# mainboard_mcu_v1_5.net
KiCad netlist of a schematic drawn in Altium Designer
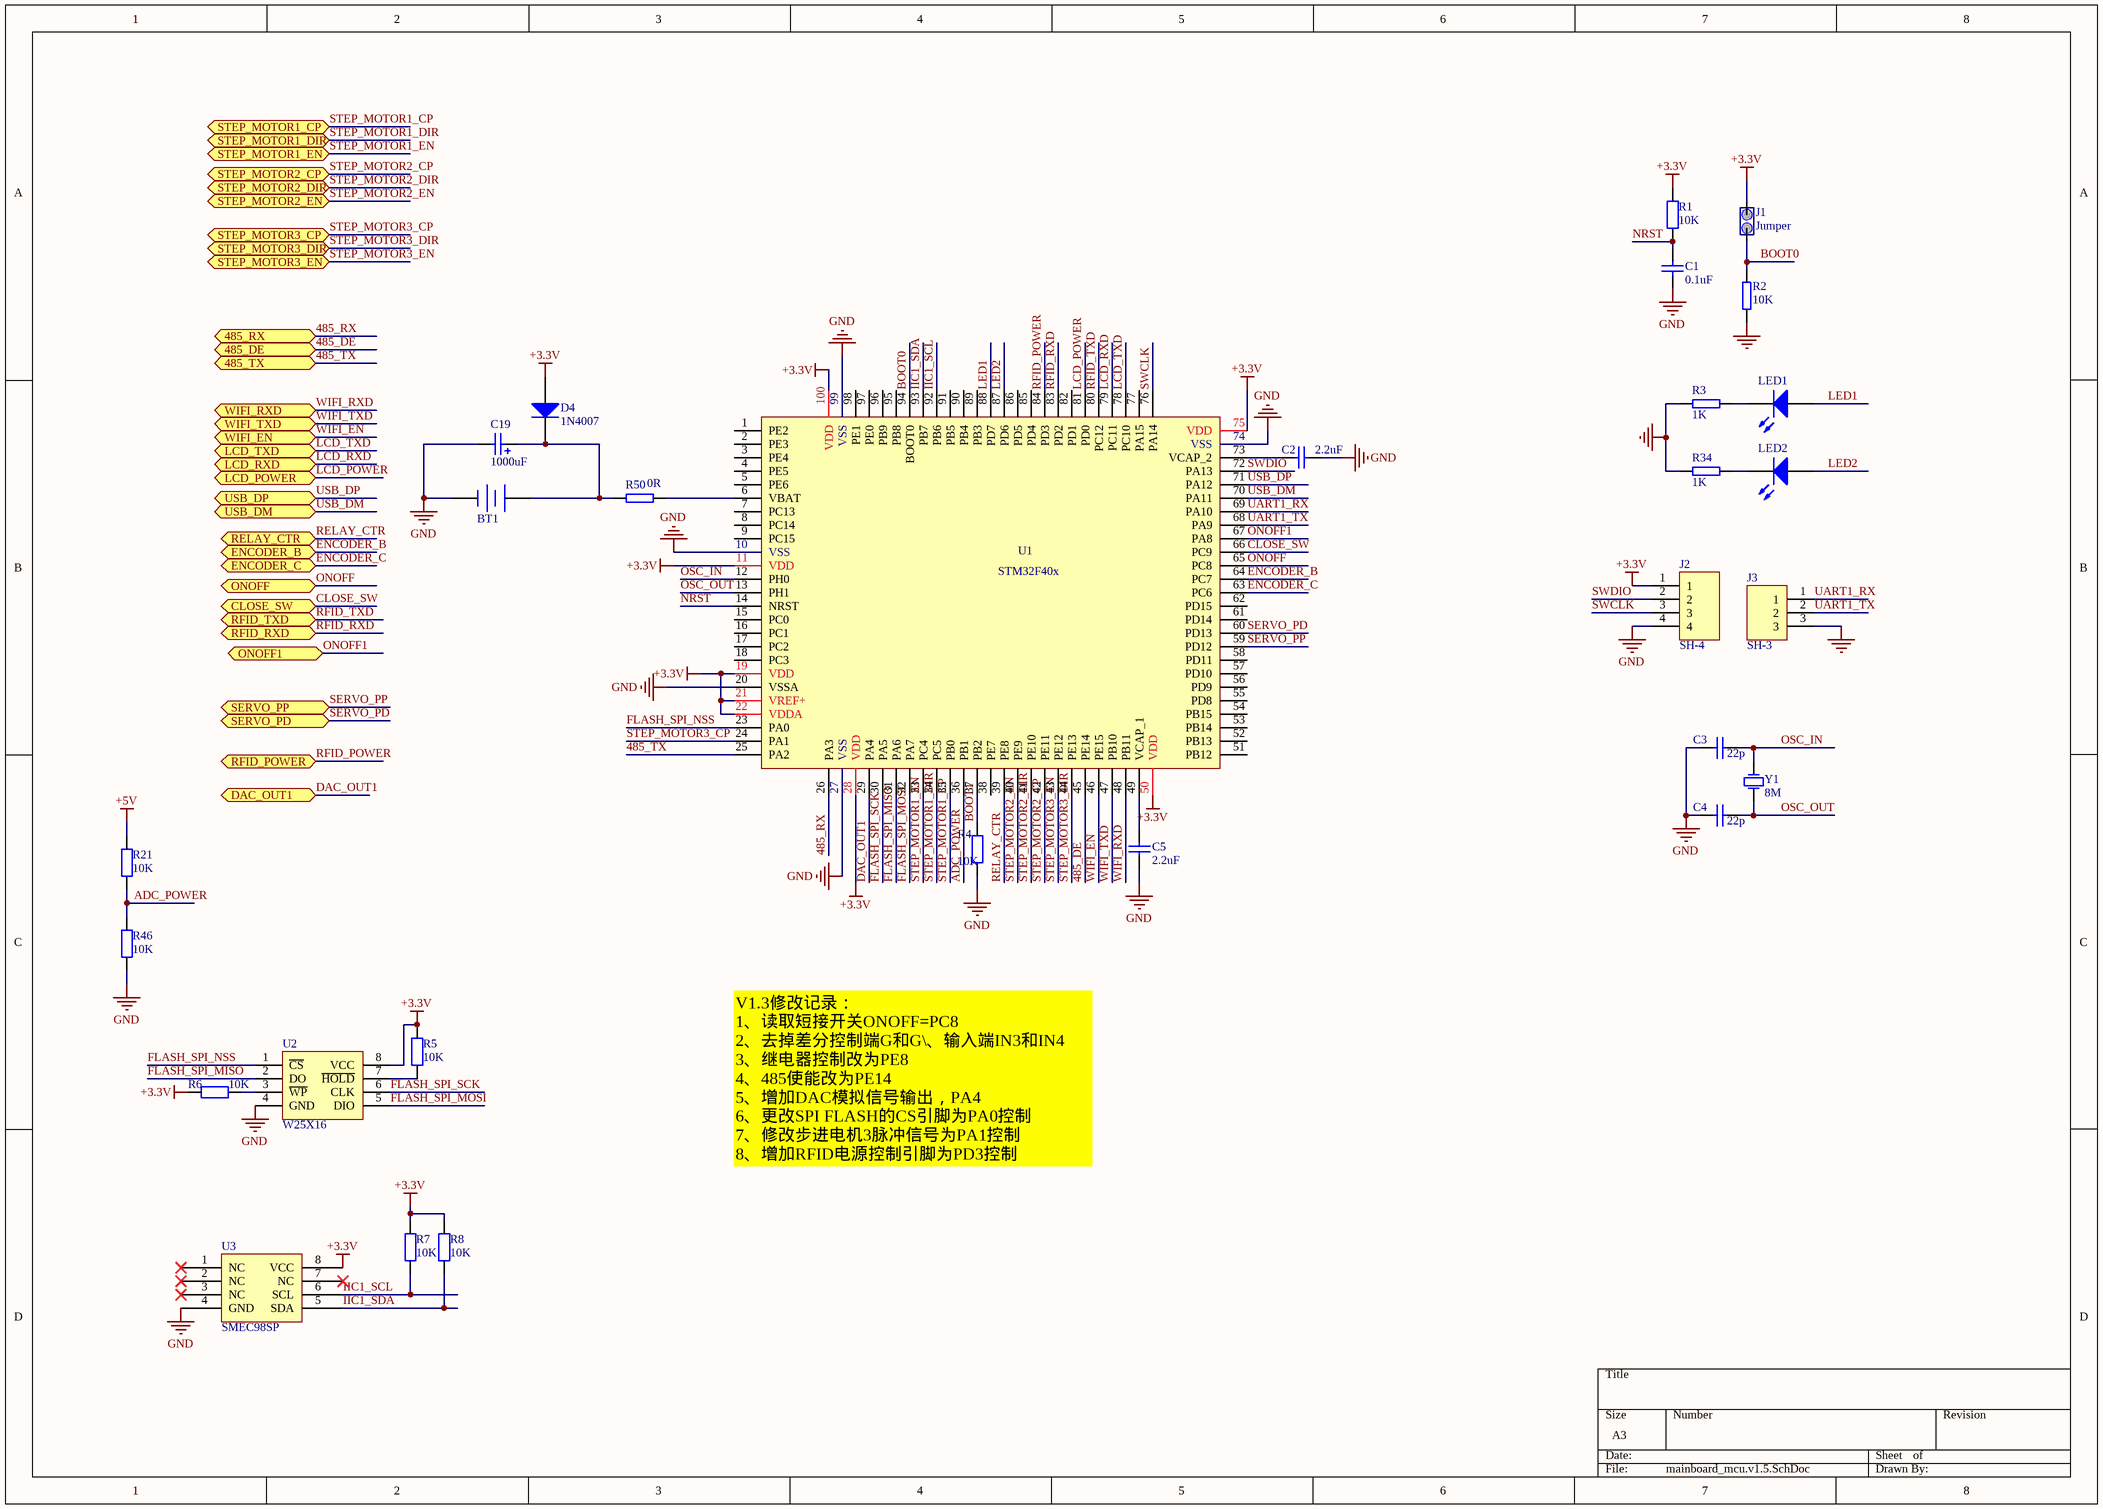
[diagram p0: mainboard_mcu.v1.5.SchDoc]

(export (version "E")
  (design (tool "Eeschema 10.0.6"))
  (components
    (comp (ref "BT1")
      (value "CR1220")
      (footprint "CR1220")
      (description "Multicell Battery")
      (fields (field (name "PUBLISHER") "Altium Limited"))
      (libsource (lib "Miscellaneous Devices") (part "Battery"))
    )
    (comp (ref "C1")
      (value "0.1uF")
      (footprint "0805")
      (description "Capacitor")
      (fields (field (name "PUBLISHER") "Altium Limited"))
      (libsource (lib "TIAN's Schlib") (part "Cap"))
    )
    (comp (ref "C2")
      (value "2.2uF")
      (footprint "0805")
      (description "Capacitor")
      (fields (field (name "PUBLISHER") "Altium Limited"))
      (libsource (lib "TIAN's Schlib") (part "Cap"))
    )
    (comp (ref "C3")
      (value "22p")
      (footprint "0805")
      (description "Capacitor")
      (fields (field (name "PUBLISHER") "Altium Limited"))
      (libsource (lib "TIAN's Schlib") (part "Cap"))
    )
    (comp (ref "C4")
      (value "22p")
      (footprint "0805")
      (description "Capacitor")
      (fields (field (name "PUBLISHER") "Altium Limited"))
      (libsource (lib "TIAN's Schlib") (part "Cap"))
    )
    (comp (ref "C5")
      (value "2.2uF")
      (footprint "0805")
      (description "Capacitor")
      (fields (field (name "PUBLISHER") "Altium Limited"))
      (libsource (lib "TIAN's Schlib") (part "Cap"))
    )
    (comp (ref "C19")
      (value "1000uF")
      (footprint "CAP_SMT_10X10")
      (description "Polarized Capacitor (Radial)")
      (fields (field (name "PUBLISHER") "Altium Limited"))
      (libsource (lib "Miscellaneous Devices") (part "Cap Pol1"))
    )
    (comp (ref "D4")
      (value "1N4007")
      (footprint "Diode_TP")
      (description "Default Diode")
      (fields (field (name "PUBLISHER") "Altium Limited"))
      (libsource (lib "Miscellaneous Devices") (part "Diode"))
    )
    (comp (ref "J1") (value "Jumper") (footprint "J254-2") (libsource (lib "Connector") (part "Jumper")))
    (comp (ref "J2") (value "SH-4") (footprint "J254-4") (libsource (lib "Connector") (part "SH-4")))
    (comp (ref "J3") (value "SH-3") (footprint "J2.54-3") (libsource (lib "Connector") (part "SH-3")))
    (comp (ref "LED1")
      (value "GREEN")
      (footprint "LED")
      (description "Typical RED, GREEN, YELLOW, AMBER GaAs LED")
      (fields (field (name "PUBLISHER") "Altium Limited"))
      (libsource (lib "Miscellaneous Devices") (part "LED2"))
    )
    (comp (ref "LED2")
      (value "GREEN")
      (footprint "LED")
      (description "Typical RED, GREEN, YELLOW, AMBER GaAs LED")
      (fields (field (name "PUBLISHER") "Altium Limited"))
      (libsource (lib "Miscellaneous Devices") (part "LED2"))
    )
    (comp (ref "R1")
      (value "10K")
      (footprint "0805")
      (description "Resistor")
      (fields (field (name "PUBLISHER") "Altium Limited"))
      (libsource (lib "") (part "Res2_1"))
    )
    (comp (ref "R2")
      (value "10K")
      (footprint "0805")
      (description "电阻")
      (libsource (lib "Component") (part "RES"))
    )
    (comp (ref "R3")
      (value "1K")
      (footprint "0805")
      (description "电阻")
      (libsource (lib "Component") (part "RES"))
    )
    (comp (ref "R4")
      (value "10K")
      (footprint "0805")
      (description "Resistor")
      (fields (field (name "PUBLISHER") "Altium Limited"))
      (libsource (lib "") (part "Res2_2"))
    )
    (comp (ref "R5")
      (value "10K")
      (footprint "0805")
      (description "Resistor")
      (fields (field (name "PUBLISHER") "Altium Limited"))
      (libsource (lib "") (part "Res2_2"))
    )
    (comp (ref "R6")
      (value "10K")
      (footprint "0805")
      (description "Resistor")
      (fields (field (name "PUBLISHER") "Altium Limited"))
      (libsource (lib "TIAN's Schlib") (part "Res2"))
    )
    (comp (ref "R7")
      (value "10K")
      (footprint "0805")
      (description "Resistor")
      (fields (field (name "PUBLISHER") "Altium Limited"))
      (libsource (lib "") (part "Res2_1"))
    )
    (comp (ref "R8")
      (value "10K")
      (footprint "0805")
      (description "Resistor")
      (fields (field (name "PUBLISHER") "Altium Limited"))
      (libsource (lib "") (part "Res2_1"))
    )
    (comp (ref "R21")
      (value "10K")
      (footprint "0805")
      (description "Resistor")
      (fields (field (name "PUBLISHER") "Altium Limited"))
      (libsource (lib "") (part "Res2_1"))
    )
    (comp (ref "R34")
      (value "1K")
      (footprint "0805")
      (description "电阻")
      (libsource (lib "Component") (part "RES"))
    )
    (comp (ref "R46")
      (value "10K")
      (footprint "0805")
      (description "Resistor")
      (fields (field (name "PUBLISHER") "Altium Limited"))
      (libsource (lib "") (part "Res2_1"))
    )
    (comp (ref "R50")
      (value "0R")
      (footprint "0805")
      (description "电阻")
      (libsource (lib "Component") (part "RES"))
    )
    (comp (ref "U1") (value "STM32F40x") (footprint "TQFP100") (libsource (lib "Chip") (part "STM32F40x")))
    (comp (ref "U2") (value "W25X16") (footprint "SOP8") (libsource (lib "Chip") (part "W25X16")))
    (comp (ref "U3") (value "SMEC98SP") (footprint "SO-8") (libsource (lib "Chip") (part "SMEC98SP")))
    (comp (ref "Y1")
      (value "8M")
      (footprint "XTAL")
      (description "Crystal Oscillator")
      (fields (field (name "PUBLISHER") "Altium Limited"))
      (libsource (lib "TIAN's Schlib") (part "X-32.768"))
    )
  )
  (nets
    (net (code "1") (name "+3.3V") (class "Default")
      (node (ref "D4") (pin "1") (pinfunction "A_1") (pintype "passive"))
      (node (ref "J1") (pin "2") (pinfunction "2_2") (pintype "passive"))
      (node (ref "J2") (pin "1") (pinfunction "1_1") (pintype "passive"))
      (node (ref "R1") (pin "2") (pinfunction "2_2") (pintype "passive"))
      (node (ref "R5") (pin "1") (pinfunction "1_1") (pintype "passive"))
      (node (ref "R6") (pin "2") (pinfunction "2_2") (pintype "passive"))
      (node (ref "R7") (pin "2") (pinfunction "2_2") (pintype "passive"))
      (node (ref "R8") (pin "2") (pinfunction "2_2") (pintype "passive"))
      (node (ref "U1") (pin "100") (pinfunction "VDD_100") (pintype "passive"))
      (node (ref "U1") (pin "11") (pinfunction "VDD_11") (pintype "passive"))
      (node (ref "U1") (pin "19") (pinfunction "VDD_19") (pintype "passive"))
      (node (ref "U1") (pin "21") (pinfunction "VREF+_21") (pintype "passive"))
      (node (ref "U1") (pin "22") (pinfunction "VDDA_22") (pintype "passive"))
      (node (ref "U1") (pin "28") (pinfunction "VDD_28") (pintype "passive"))
      (node (ref "U1") (pin "50") (pinfunction "VDD_50") (pintype "passive"))
      (node (ref "U1") (pin "75") (pinfunction "VDD_75") (pintype "passive"))
      (node (ref "U2") (pin "8") (pinfunction "VCC_8") (pintype "passive"))
      (node (ref "U3") (pin "8") (pinfunction "VCC_8") (pintype "passive"))
    )
    (net (code "2") (name "+5V") (class "Default")
      (node (ref "R21") (pin "2") (pinfunction "2_2") (pintype "passive"))
    )
    (net (code "3") (name "/485_DE") (class "Default")
      (node (ref "U1") (pin "45") (pinfunction "PE14_45") (pintype "passive"))
    )
    (net (code "4") (name "/485_RX") (class "Default")
      (node (ref "U1") (pin "26") (pinfunction "PA3_26") (pintype "passive"))
    )
    (net (code "5") (name "/485_TX") (class "Default")
      (node (ref "U1") (pin "25") (pinfunction "PA2_25") (pintype "passive"))
    )
    (net (code "6") (name "/ADC_POWER") (class "Default")
      (node (ref "R21") (pin "1") (pinfunction "1_1") (pintype "passive"))
      (node (ref "R46") (pin "2") (pinfunction "2_2") (pintype "passive"))
      (node (ref "U1") (pin "36") (pinfunction "PB1_36") (pintype "passive"))
    )
    (net (code "7") (name "/BOOT0") (class "Default")
      (node (ref "J1") (pin "1") (pinfunction "1_1") (pintype "passive"))
      (node (ref "R2") (pin "1") (pinfunction "1_1") (pintype "passive"))
      (node (ref "U1") (pin "94") (pinfunction "BOOT0_94") (pintype "passive"))
    )
    (net (code "8") (name "/BOOT1") (class "Default")
      (node (ref "R4") (pin "1") (pinfunction "1_1") (pintype "passive"))
      (node (ref "U1") (pin "37") (pinfunction "PB2_37") (pintype "passive"))
    )
    (net (code "9") (name "/CLOSE_SW") (class "Default")
      (node (ref "U1") (pin "66") (pinfunction "PC9_66") (pintype "passive"))
    )
    (net (code "10") (name "/DAC_OUT1") (class "Default")
      (node (ref "U1") (pin "29") (pinfunction "PA4_29") (pintype "passive"))
    )
    (net (code "11") (name "/ENCODER_B") (class "Default")
      (node (ref "U1") (pin "64") (pinfunction "PC7_64") (pintype "passive"))
    )
    (net (code "12") (name "/ENCODER_C") (class "Default")
      (node (ref "U1") (pin "63") (pinfunction "PC6_63") (pintype "passive"))
    )
    (net (code "13") (name "/FLASH_SPI_MISO") (class "Default")
      (node (ref "U1") (pin "31") (pinfunction "PA6_31") (pintype "passive"))
      (node (ref "U2") (pin "2") (pinfunction "DO_2") (pintype "passive"))
    )
    (net (code "14") (name "/FLASH_SPI_MOSI") (class "Default")
      (node (ref "U1") (pin "32") (pinfunction "PA7_32") (pintype "passive"))
      (node (ref "U2") (pin "5") (pinfunction "DIO_5") (pintype "passive"))
    )
    (net (code "15") (name "/FLASH_SPI_NSS") (class "Default")
      (node (ref "U1") (pin "23") (pinfunction "PA0_23") (pintype "passive"))
      (node (ref "U2") (pin "1") (pinfunction "~{CS}_1") (pintype "passive"))
    )
    (net (code "16") (name "/FLASH_SPI_SCK") (class "Default")
      (node (ref "U1") (pin "30") (pinfunction "PA5_30") (pintype "passive"))
      (node (ref "U2") (pin "6") (pinfunction "CLK_6") (pintype "passive"))
    )
    (net (code "17") (name "/IIC1_SCL") (class "Default")
      (node (ref "R7") (pin "1") (pinfunction "1_1") (pintype "passive"))
      (node (ref "U1") (pin "92") (pinfunction "PB6_92") (pintype "passive"))
      (node (ref "U3") (pin "6") (pinfunction "SCL_6") (pintype "passive"))
    )
    (net (code "18") (name "/IIC1_SDA") (class "Default")
      (node (ref "R8") (pin "1") (pinfunction "1_1") (pintype "passive"))
      (node (ref "U1") (pin "93") (pinfunction "PB7_93") (pintype "passive"))
      (node (ref "U3") (pin "5") (pinfunction "SDA_5") (pintype "passive"))
    )
    (net (code "19") (name "/LCD_POWER") (class "Default")
      (node (ref "U1") (pin "81") (pinfunction "PD0_81") (pintype "passive"))
    )
    (net (code "20") (name "/LCD_RXD") (class "Default")
      (node (ref "U1") (pin "79") (pinfunction "PC11_79") (pintype "passive"))
    )
    (net (code "21") (name "/LCD_TXD") (class "Default")
      (node (ref "U1") (pin "78") (pinfunction "PC10_78") (pintype "passive"))
    )
    (net (code "22") (name "/LED1") (class "Default")
      (node (ref "LED1") (pin "1") (pinfunction "A_1") (pintype "passive"))
      (node (ref "U1") (pin "88") (pinfunction "PD7_88") (pintype "passive"))
    )
    (net (code "23") (name "/LED2") (class "Default")
      (node (ref "LED2") (pin "1") (pinfunction "A_1") (pintype "passive"))
      (node (ref "U1") (pin "87") (pinfunction "PD6_87") (pintype "passive"))
    )
    (net (code "24") (name "/NRST") (class "Default")
      (node (ref "C1") (pin "2") (pinfunction "2_2") (pintype "passive"))
      (node (ref "R1") (pin "1") (pinfunction "1_1") (pintype "passive"))
      (node (ref "U1") (pin "14") (pinfunction "NRST_14") (pintype "passive"))
    )
    (net (code "25") (name "/ONOFF") (class "Default")
      (node (ref "U1") (pin "65") (pinfunction "PC8_65") (pintype "passive"))
    )
    (net (code "26") (name "/ONOFF1") (class "Default")
      (node (ref "U1") (pin "67") (pinfunction "PA8_67") (pintype "passive"))
    )
    (net (code "27") (name "/OSC_IN") (class "Default")
      (node (ref "C3") (pin "1") (pinfunction "1_1") (pintype "passive"))
      (node (ref "U1") (pin "12") (pinfunction "PH0_12") (pintype "passive"))
      (node (ref "Y1") (pin "2") (pinfunction "OSC2_2") (pintype "passive"))
    )
    (net (code "28") (name "/OSC_OUT") (class "Default")
      (node (ref "C4") (pin "1") (pinfunction "1_1") (pintype "passive"))
      (node (ref "U1") (pin "13") (pinfunction "PH1_13") (pintype "passive"))
      (node (ref "Y1") (pin "1") (pinfunction "OSC1_1") (pintype "passive"))
    )
    (net (code "29") (name "/RELAY_CTR") (class "Default")
      (node (ref "U1") (pin "39") (pinfunction "PE8_39") (pintype "passive"))
    )
    (net (code "30") (name "/RFID_POWER") (class "Default")
      (node (ref "U1") (pin "84") (pinfunction "PD3_84") (pintype "passive"))
    )
    (net (code "31") (name "/RFID_RXD") (class "Default")
      (node (ref "U1") (pin "83") (pinfunction "PD2_83") (pintype "passive"))
    )
    (net (code "32") (name "/RFID_TXD") (class "Default")
      (node (ref "U1") (pin "80") (pinfunction "PC12_80") (pintype "passive"))
    )
    (net (code "33") (name "/SERVO_PD") (class "Default")
      (node (ref "U1") (pin "60") (pinfunction "PD13_60") (pintype "passive"))
    )
    (net (code "34") (name "/SERVO_PP") (class "Default")
      (node (ref "U1") (pin "59") (pinfunction "PD12_59") (pintype "passive"))
    )
    (net (code "35") (name "/STEP_MOTOR1_CP") (class "Default")
      (node (ref "U1") (pin "35") (pinfunction "PB0_35") (pintype "passive"))
    )
    (net (code "36") (name "/STEP_MOTOR1_DIR") (class "Default")
      (node (ref "U1") (pin "34") (pinfunction "PC5_34") (pintype "passive"))
    )
    (net (code "37") (name "/STEP_MOTOR1_EN") (class "Default")
      (node (ref "U1") (pin "33") (pinfunction "PC4_33") (pintype "passive"))
    )
    (net (code "38") (name "/STEP_MOTOR2_CP") (class "Default")
      (node (ref "U1") (pin "42") (pinfunction "PE11_42") (pintype "passive"))
    )
    (net (code "39") (name "/STEP_MOTOR2_DIR") (class "Default")
      (node (ref "U1") (pin "41") (pinfunction "PE10_41") (pintype "passive"))
    )
    (net (code "40") (name "/STEP_MOTOR2_EN") (class "Default")
      (node (ref "U1") (pin "40") (pinfunction "PE9_40") (pintype "passive"))
    )
    (net (code "41") (name "/STEP_MOTOR3_CP") (class "Default")
      (node (ref "U1") (pin "24") (pinfunction "PA1_24") (pintype "passive"))
    )
    (net (code "42") (name "/STEP_MOTOR3_DIR") (class "Default")
      (node (ref "U1") (pin "44") (pinfunction "PE13_44") (pintype "passive"))
    )
    (net (code "43") (name "/STEP_MOTOR3_EN") (class "Default")
      (node (ref "U1") (pin "43") (pinfunction "PE12_43") (pintype "passive"))
    )
    (net (code "44") (name "/SWCLK") (class "Default")
      (node (ref "J2") (pin "3") (pinfunction "3_3") (pintype "passive"))
      (node (ref "U1") (pin "76") (pinfunction "PA14_76") (pintype "passive"))
    )
    (net (code "45") (name "/SWDIO") (class "Default")
      (node (ref "J2") (pin "2") (pinfunction "2_2") (pintype "passive"))
      (node (ref "U1") (pin "72") (pinfunction "PA13_72") (pintype "passive"))
    )
    (net (code "46") (name "/UART1_RX") (class "Default")
      (node (ref "J3") (pin "1") (pinfunction "1_1") (pintype "passive"))
      (node (ref "U1") (pin "69") (pinfunction "PA10_69") (pintype "passive"))
    )
    (net (code "47") (name "/UART1_TX") (class "Default")
      (node (ref "J3") (pin "2") (pinfunction "2_2") (pintype "passive"))
      (node (ref "U1") (pin "68") (pinfunction "PA9_68") (pintype "passive"))
    )
    (net (code "48") (name "/USB_DM") (class "Default")
      (node (ref "U1") (pin "70") (pinfunction "PA11_70") (pintype "passive"))
    )
    (net (code "49") (name "/USB_DP") (class "Default")
      (node (ref "U1") (pin "71") (pinfunction "PA12_71") (pintype "passive"))
    )
    (net (code "50") (name "/WIFI_EN") (class "Default")
      (node (ref "U1") (pin "46") (pinfunction "PE15_46") (pintype "passive"))
    )
    (net (code "51") (name "/WIFI_RXD") (class "Default")
      (node (ref "U1") (pin "48") (pinfunction "PB11_48") (pintype "passive"))
    )
    (net (code "52") (name "/WIFI_TXD") (class "Default")
      (node (ref "U1") (pin "47") (pinfunction "PB10_47") (pintype "passive"))
    )
    (net (code "53") (name "GND") (class "Default")
      (node (ref "BT1") (pin "2") (pinfunction "-_2") (pintype "passive"))
      (node (ref "C1") (pin "1") (pinfunction "1_1") (pintype "passive"))
      (node (ref "C19") (pin "2") (pinfunction "2_2") (pintype "passive"))
      (node (ref "C2") (pin "1") (pinfunction "1_1") (pintype "passive"))
      (node (ref "C3") (pin "2") (pinfunction "2_2") (pintype "passive"))
      (node (ref "C4") (pin "2") (pinfunction "2_2") (pintype "passive"))
      (node (ref "C5") (pin "2") (pinfunction "2_2") (pintype "passive"))
      (node (ref "J2") (pin "4") (pinfunction "4_4") (pintype "passive"))
      (node (ref "J3") (pin "3") (pinfunction "3_3") (pintype "passive"))
      (node (ref "R2") (pin "2") (pinfunction "2_2") (pintype "passive"))
      (node (ref "R3") (pin "2") (pinfunction "2_2") (pintype "passive"))
      (node (ref "R34") (pin "2") (pinfunction "2_2") (pintype "passive"))
      (node (ref "R4") (pin "2") (pinfunction "2_2") (pintype "passive"))
      (node (ref "R46") (pin "1") (pinfunction "1_1") (pintype "passive"))
      (node (ref "U1") (pin "10") (pinfunction "VSS_10") (pintype "passive"))
      (node (ref "U1") (pin "20") (pinfunction "VSSA_20") (pintype "passive"))
      (node (ref "U1") (pin "27") (pinfunction "VSS_27") (pintype "passive"))
      (node (ref "U1") (pin "74") (pinfunction "VSS_74") (pintype "passive"))
      (node (ref "U1") (pin "99") (pinfunction "VSS_99") (pintype "passive"))
      (node (ref "U2") (pin "4") (pinfunction "GND_4") (pintype "passive"))
      (node (ref "U3") (pin "4") (pinfunction "GND_4") (pintype "passive"))
    )
    (net (code "54") (name "Net-(BT1-+)") (class "Default")
      (node (ref "BT1") (pin "1") (pinfunction "+_1") (pintype "passive"))
      (node (ref "C19") (pin "1") (pinfunction "1_1") (pintype "passive"))
      (node (ref "D4") (pin "2") (pinfunction "K_2") (pintype "passive"))
      (node (ref "R50") (pin "1") (pinfunction "1_1") (pintype "passive"))
    )
    (net (code "55") (name "Net-(LED1-K)") (class "Default")
      (node (ref "LED1") (pin "2") (pinfunction "K_2") (pintype "passive"))
      (node (ref "R3") (pin "1") (pinfunction "1_1") (pintype "passive"))
    )
    (net (code "56") (name "Net-(LED2-K)") (class "Default")
      (node (ref "LED2") (pin "2") (pinfunction "K_2") (pintype "passive"))
      (node (ref "R34") (pin "1") (pinfunction "1_1") (pintype "passive"))
    )
    (net (code "57") (name "Net-(U1-VBAT)") (class "Default")
      (node (ref "R50") (pin "2") (pinfunction "2_2") (pintype "passive"))
      (node (ref "U1") (pin "6") (pinfunction "VBAT_6") (pintype "passive"))
    )
    (net (code "58") (name "Net-(U1-VCAP_1)") (class "Default")
      (node (ref "C5") (pin "1") (pinfunction "1_1") (pintype "passive"))
      (node (ref "U1") (pin "49") (pinfunction "VCAP_1_49") (pintype "passive"))
    )
    (net (code "59") (name "Net-(U1-VCAP_2)") (class "Default")
      (node (ref "C2") (pin "2") (pinfunction "2_2") (pintype "passive"))
      (node (ref "U1") (pin "73") (pinfunction "VCAP_2_73") (pintype "passive"))
    )
    (net (code "60") (name "Net-(U2-~{HOLD})") (class "Default")
      (node (ref "R5") (pin "2") (pinfunction "2_2") (pintype "passive"))
      (node (ref "U2") (pin "7") (pinfunction "~{HOLD}_7") (pintype "passive"))
    )
    (net (code "61") (name "Net-(U2-~{WP})") (class "Default")
      (node (ref "R6") (pin "1") (pinfunction "1_1") (pintype "passive"))
      (node (ref "U2") (pin "3") (pinfunction "~{WP}_3") (pintype "passive"))
    )
    (net (code "62") (name "unconnected-(U1-PA15-Pad77)") (class "Default")
      (node (ref "U1") (pin "77") (pinfunction "PA15_77") (pintype "passive"))
    )
    (net (code "63") (name "unconnected-(U1-PB3-Pad89)") (class "Default")
      (node (ref "U1") (pin "89") (pinfunction "PB3_89") (pintype "passive"))
    )
    (net (code "64") (name "unconnected-(U1-PB4-Pad90)") (class "Default")
      (node (ref "U1") (pin "90") (pinfunction "PB4_90") (pintype "passive"))
    )
    (net (code "65") (name "unconnected-(U1-PB5-Pad91)") (class "Default")
      (node (ref "U1") (pin "91") (pinfunction "PB5_91") (pintype "passive"))
    )
    (net (code "66") (name "unconnected-(U1-PB8-Pad95)") (class "Default")
      (node (ref "U1") (pin "95") (pinfunction "PB8_95") (pintype "passive"))
    )
    (net (code "67") (name "unconnected-(U1-PB9-Pad96)") (class "Default")
      (node (ref "U1") (pin "96") (pinfunction "PB9_96") (pintype "passive"))
    )
    (net (code "68") (name "unconnected-(U1-PB12-Pad51)") (class "Default")
      (node (ref "U1") (pin "51") (pinfunction "PB12_51") (pintype "passive"))
    )
    (net (code "69") (name "unconnected-(U1-PB13-Pad52)") (class "Default")
      (node (ref "U1") (pin "52") (pinfunction "PB13_52") (pintype "passive"))
    )
    (net (code "70") (name "unconnected-(U1-PB14-Pad53)") (class "Default")
      (node (ref "U1") (pin "53") (pinfunction "PB14_53") (pintype "passive"))
    )
    (net (code "71") (name "unconnected-(U1-PB15-Pad54)") (class "Default")
      (node (ref "U1") (pin "54") (pinfunction "PB15_54") (pintype "passive"))
    )
    (net (code "72") (name "unconnected-(U1-PC0-Pad15)") (class "Default")
      (node (ref "U1") (pin "15") (pinfunction "PC0_15") (pintype "passive"))
    )
    (net (code "73") (name "unconnected-(U1-PC1-Pad16)") (class "Default")
      (node (ref "U1") (pin "16") (pinfunction "PC1_16") (pintype "passive"))
    )
    (net (code "74") (name "unconnected-(U1-PC2-Pad17)") (class "Default")
      (node (ref "U1") (pin "17") (pinfunction "PC2_17") (pintype "passive"))
    )
    (net (code "75") (name "unconnected-(U1-PC3-Pad18)") (class "Default")
      (node (ref "U1") (pin "18") (pinfunction "PC3_18") (pintype "passive"))
    )
    (net (code "76") (name "unconnected-(U1-PC13-Pad7)") (class "Default")
      (node (ref "U1") (pin "7") (pinfunction "PC13_7") (pintype "passive"))
    )
    (net (code "77") (name "unconnected-(U1-PC14-Pad8)") (class "Default")
      (node (ref "U1") (pin "8") (pinfunction "PC14_8") (pintype "passive"))
    )
    (net (code "78") (name "unconnected-(U1-PC15-Pad9)") (class "Default")
      (node (ref "U1") (pin "9") (pinfunction "PC15_9") (pintype "passive"))
    )
    (net (code "79") (name "unconnected-(U1-PD1-Pad82)") (class "Default")
      (node (ref "U1") (pin "82") (pinfunction "PD1_82") (pintype "passive"))
    )
    (net (code "80") (name "unconnected-(U1-PD4-Pad85)") (class "Default")
      (node (ref "U1") (pin "85") (pinfunction "PD4_85") (pintype "passive"))
    )
    (net (code "81") (name "unconnected-(U1-PD5-Pad86)") (class "Default")
      (node (ref "U1") (pin "86") (pinfunction "PD5_86") (pintype "passive"))
    )
    (net (code "82") (name "unconnected-(U1-PD8-Pad55)") (class "Default")
      (node (ref "U1") (pin "55") (pinfunction "PD8_55") (pintype "passive"))
    )
    (net (code "83") (name "unconnected-(U1-PD9-Pad56)") (class "Default")
      (node (ref "U1") (pin "56") (pinfunction "PD9_56") (pintype "passive"))
    )
    (net (code "84") (name "unconnected-(U1-PD10-Pad57)") (class "Default")
      (node (ref "U1") (pin "57") (pinfunction "PD10_57") (pintype "passive"))
    )
    (net (code "85") (name "unconnected-(U1-PD11-Pad58)") (class "Default")
      (node (ref "U1") (pin "58") (pinfunction "PD11_58") (pintype "passive"))
    )
    (net (code "86") (name "unconnected-(U1-PD14-Pad61)") (class "Default")
      (node (ref "U1") (pin "61") (pinfunction "PD14_61") (pintype "passive"))
    )
    (net (code "87") (name "unconnected-(U1-PD15-Pad62)") (class "Default")
      (node (ref "U1") (pin "62") (pinfunction "PD15_62") (pintype "passive"))
    )
    (net (code "88") (name "unconnected-(U1-PE0-Pad97)") (class "Default")
      (node (ref "U1") (pin "97") (pinfunction "PE0_97") (pintype "passive"))
    )
    (net (code "89") (name "unconnected-(U1-PE1-Pad98)") (class "Default")
      (node (ref "U1") (pin "98") (pinfunction "PE1_98") (pintype "passive"))
    )
    (net (code "90") (name "unconnected-(U1-PE2-Pad1)") (class "Default")
      (node (ref "U1") (pin "1") (pinfunction "PE2_1") (pintype "passive"))
    )
    (net (code "91") (name "unconnected-(U1-PE3-Pad2)") (class "Default")
      (node (ref "U1") (pin "2") (pinfunction "PE3_2") (pintype "passive"))
    )
    (net (code "92") (name "unconnected-(U1-PE4-Pad3)") (class "Default")
      (node (ref "U1") (pin "3") (pinfunction "PE4_3") (pintype "passive"))
    )
    (net (code "93") (name "unconnected-(U1-PE5-Pad4)") (class "Default")
      (node (ref "U1") (pin "4") (pinfunction "PE5_4") (pintype "passive"))
    )
    (net (code "94") (name "unconnected-(U1-PE6-Pad5)") (class "Default")
      (node (ref "U1") (pin "5") (pinfunction "PE6_5") (pintype "passive"))
    )
    (net (code "95") (name "unconnected-(U1-PE7-Pad38)") (class "Default")
      (node (ref "U1") (pin "38") (pinfunction "PE7_38") (pintype "passive"))
    )
    (net (code "96") (name "unconnected-(U3-NC-Pad1)") (class "Default")
      (node (ref "U3") (pin "1") (pinfunction "NC_1") (pintype "passive+no_connect"))
    )
    (net (code "97") (name "unconnected-(U3-NC-Pad2)") (class "Default")
      (node (ref "U3") (pin "2") (pinfunction "NC_2") (pintype "passive+no_connect"))
    )
    (net (code "98") (name "unconnected-(U3-NC-Pad3)") (class "Default")
      (node (ref "U3") (pin "3") (pinfunction "NC_3") (pintype "passive+no_connect"))
    )
    (net (code "99") (name "unconnected-(U3-NC-Pad7)") (class "Default")
      (node (ref "U3") (pin "7") (pinfunction "NC_7") (pintype "passive+no_connect"))
    )
  )
)
